# M219X.net
KiCad netlist of a schematic drawn in EAGLE
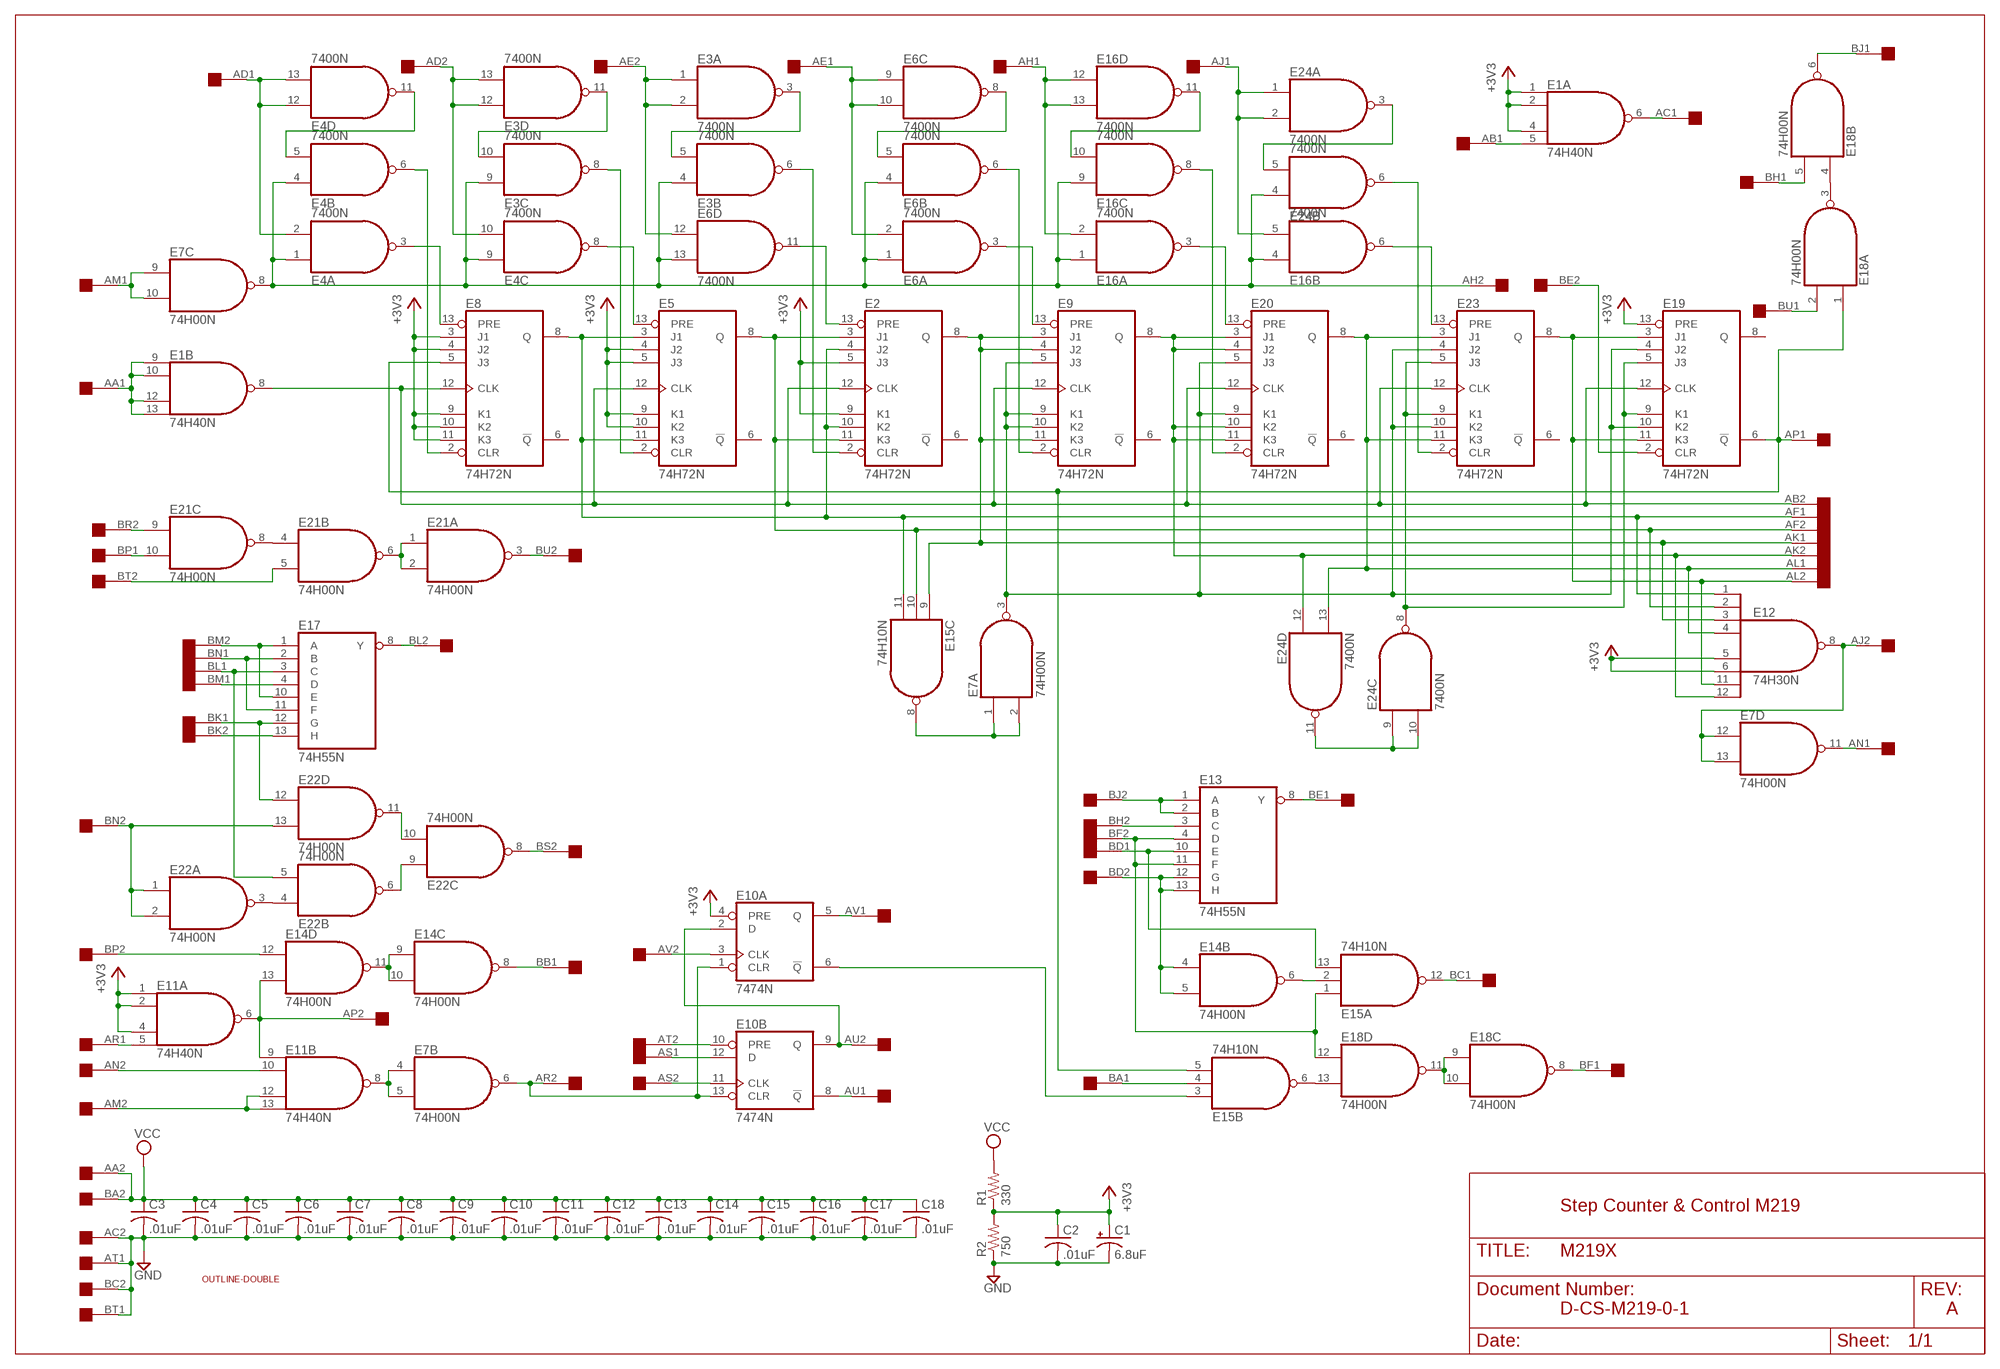
[diagram p0: schematic, sheet 1]

(export (version "E")
  (design (tool "Eeschema 10.0.6"))
  (components
    (comp (ref "C1")
      (value "6.8uF")
      (footprint "eagle-import:E12-8")
      (libsource (lib "eagle-import") (part "CPOL-USE20-8AXIAL"))
    )
    (comp (ref "C2")
      (value ".01uF")
      (footprint "eagle-import:C050-025X075")
      (libsource (lib "eagle-import") (part "C-US050-025X075"))
    )
    (comp (ref "C3")
      (value ".01uF")
      (footprint "eagle-import:C050-025X075")
      (libsource (lib "eagle-import") (part "C-US050-025X075"))
    )
    (comp (ref "C4")
      (value ".01uF")
      (footprint "eagle-import:C050-025X075")
      (libsource (lib "eagle-import") (part "C-US050-025X075"))
    )
    (comp (ref "C5")
      (value ".01uF")
      (footprint "eagle-import:C050-025X075")
      (libsource (lib "eagle-import") (part "C-US050-025X075"))
    )
    (comp (ref "C6")
      (value ".01uF")
      (footprint "eagle-import:C050-025X075")
      (libsource (lib "eagle-import") (part "C-US050-025X075"))
    )
    (comp (ref "C7")
      (value ".01uF")
      (footprint "eagle-import:C050-025X075")
      (libsource (lib "eagle-import") (part "C-US050-025X075"))
    )
    (comp (ref "C8")
      (value ".01uF")
      (footprint "eagle-import:C050-025X075")
      (libsource (lib "eagle-import") (part "C-US050-025X075"))
    )
    (comp (ref "C9")
      (value ".01uF")
      (footprint "eagle-import:C050-025X075")
      (libsource (lib "eagle-import") (part "C-US050-025X075"))
    )
    (comp (ref "C10")
      (value ".01uF")
      (footprint "eagle-import:C050-025X075")
      (libsource (lib "eagle-import") (part "C-US050-025X075"))
    )
    (comp (ref "C11")
      (value ".01uF")
      (footprint "eagle-import:C050-025X075")
      (libsource (lib "eagle-import") (part "C-US050-025X075"))
    )
    (comp (ref "C12")
      (value ".01uF")
      (footprint "eagle-import:C050-025X075")
      (libsource (lib "eagle-import") (part "C-US050-025X075"))
    )
    (comp (ref "C13")
      (value ".01uF")
      (footprint "eagle-import:C050-025X075")
      (libsource (lib "eagle-import") (part "C-US050-025X075"))
    )
    (comp (ref "C14")
      (value ".01uF")
      (footprint "eagle-import:C050-025X075")
      (libsource (lib "eagle-import") (part "C-US050-025X075"))
    )
    (comp (ref "C15")
      (value ".01uF")
      (footprint "eagle-import:C050-025X075")
      (libsource (lib "eagle-import") (part "C-US050-025X075"))
    )
    (comp (ref "C16")
      (value ".01uF")
      (footprint "eagle-import:C050-025X075")
      (libsource (lib "eagle-import") (part "C-US050-025X075"))
    )
    (comp (ref "C17")
      (value ".01uF")
      (footprint "eagle-import:C050-025X075")
      (libsource (lib "eagle-import") (part "C-US050-025X075"))
    )
    (comp (ref "C18")
      (value ".01uF")
      (footprint "eagle-import:C050-025X075")
      (libsource (lib "eagle-import") (part "C-US050-025X075"))
    )
    (comp (ref "E1")
      (value "74H40N")
      (footprint "eagle-import:DIL14")
      (libsource (lib "eagle-import") (part "7440NS"))
    )
    (comp (ref "E2")
      (value "74H72N")
      (footprint "eagle-import:DIL14")
      (libsource (lib "eagle-import") (part "7472N"))
    )
    (comp (ref "E3")
      (value "7400N")
      (footprint "eagle-import:DIL14")
      (libsource (lib "eagle-import") (part "7400NS"))
    )
    (comp (ref "E4")
      (value "7400N")
      (footprint "eagle-import:DIL14")
      (libsource (lib "eagle-import") (part "7400NS"))
    )
    (comp (ref "E5")
      (value "74H72N")
      (footprint "eagle-import:DIL14")
      (libsource (lib "eagle-import") (part "7472N"))
    )
    (comp (ref "E6")
      (value "7400N")
      (footprint "eagle-import:DIL14")
      (libsource (lib "eagle-import") (part "7400NS"))
    )
    (comp (ref "E7")
      (value "74H00N")
      (footprint "eagle-import:DIL14")
      (libsource (lib "eagle-import") (part "7400NS"))
    )
    (comp (ref "E8")
      (value "74H72N")
      (footprint "eagle-import:DIL14")
      (libsource (lib "eagle-import") (part "7472N"))
    )
    (comp (ref "E9")
      (value "74H72N")
      (footprint "eagle-import:DIL14")
      (libsource (lib "eagle-import") (part "7472N"))
    )
    (comp (ref "E10")
      (value "7474N")
      (footprint "eagle-import:DIL14")
      (libsource (lib "eagle-import") (part "7474NS"))
    )
    (comp (ref "E11")
      (value "74H40N")
      (footprint "eagle-import:DIL14")
      (libsource (lib "eagle-import") (part "7440NS"))
    )
    (comp (ref "E12")
      (value "74H30N")
      (footprint "eagle-import:DIL14")
      (libsource (lib "eagle-import") (part "7430NS"))
    )
    (comp (ref "E13")
      (value "74H55N")
      (footprint "eagle-import:DIL14")
      (libsource (lib "eagle-import") (part "7455NLS"))
    )
    (comp (ref "E14")
      (value "74H00N")
      (footprint "eagle-import:DIL14")
      (libsource (lib "eagle-import") (part "7400NS"))
    )
    (comp (ref "E15")
      (value "74H10N")
      (footprint "eagle-import:DIL14")
      (libsource (lib "eagle-import") (part "7410NS"))
    )
    (comp (ref "E16")
      (value "7400N")
      (footprint "eagle-import:DIL14")
      (libsource (lib "eagle-import") (part "7400NS"))
    )
    (comp (ref "E17")
      (value "74H55N")
      (footprint "eagle-import:DIL14")
      (libsource (lib "eagle-import") (part "7455NLS"))
    )
    (comp (ref "E18")
      (value "74H00N")
      (footprint "eagle-import:DIL14")
      (libsource (lib "eagle-import") (part "7400NS"))
    )
    (comp (ref "E19")
      (value "74H72N")
      (footprint "eagle-import:DIL14")
      (libsource (lib "eagle-import") (part "7472N"))
    )
    (comp (ref "E20")
      (value "74H72N")
      (footprint "eagle-import:DIL14")
      (libsource (lib "eagle-import") (part "7472N"))
    )
    (comp (ref "E21")
      (value "74H00N")
      (footprint "eagle-import:DIL14")
      (libsource (lib "eagle-import") (part "7400NS"))
    )
    (comp (ref "E22")
      (value "74H00N")
      (footprint "eagle-import:DIL14")
      (libsource (lib "eagle-import") (part "7400NS"))
    )
    (comp (ref "E23")
      (value "74H72N")
      (footprint "eagle-import:DIL14")
      (libsource (lib "eagle-import") (part "7472N"))
    )
    (comp (ref "E24")
      (value "7400N")
      (footprint "eagle-import:DIL14")
      (libsource (lib "eagle-import") (part "7400NS"))
    )
    (comp (ref "R1")
      (value "330")
      (footprint "eagle-import:0207_10")
      (libsource (lib "eagle-import") (part "R-US_0207/10"))
    )
    (comp (ref "R2")
      (value "750")
      (footprint "eagle-import:0207_10")
      (libsource (lib "eagle-import") (part "R-US_0207/10"))
    )
    (comp (ref "U$1")
      (value "OUTLINE-DOUBLE")
      (footprint "eagle-import:DOUBLE")
      (libsource (lib "eagle-import") (part "OUTLINE-DOUBLE"))
    )
    (comp (ref "U$3")
      (value "DOUBLE")
      (footprint "eagle-import:EDGE-CON4")
      (libsource (lib "eagle-import") (part "DOUBLE"))
    )
  )
  (nets
    (net (code "1") (name "+3V3") (class "Default")
      (node (ref "C1") (pin "+") (pinfunction "+_+") (pintype "passive"))
      (node (ref "C2") (pin "1") (pinfunction "1_1") (pintype "passive"))
      (node (ref "E1") (pin "1") (pinfunction "I0_1") (pintype "input"))
      (node (ref "E1") (pin "2") (pinfunction "I1_2") (pintype "input"))
      (node (ref "E1") (pin "4") (pinfunction "I2_4") (pintype "input"))
      (node (ref "E10") (pin "4") (pinfunction "PRE_4") (pintype "input"))
      (node (ref "E11") (pin "1") (pinfunction "I0_1") (pintype "input"))
      (node (ref "E11") (pin "2") (pinfunction "I1_2") (pintype "input"))
      (node (ref "E11") (pin "4") (pinfunction "I2_4") (pintype "input"))
      (node (ref "E12") (pin "5") (pinfunction "I4_5") (pintype "input"))
      (node (ref "E12") (pin "6") (pinfunction "I5_6") (pintype "input"))
      (node (ref "E19") (pin "13") (pinfunction "PRE_13") (pintype "input"))
      (node (ref "E2") (pin "5") (pinfunction "J3_5") (pintype "input"))
      (node (ref "E2") (pin "9") (pinfunction "K1_9") (pintype "input"))
      (node (ref "E5") (pin "10") (pinfunction "K2_10") (pintype "input"))
      (node (ref "E5") (pin "4") (pinfunction "J2_4") (pintype "input"))
      (node (ref "E5") (pin "5") (pinfunction "J3_5") (pintype "input"))
      (node (ref "E5") (pin "9") (pinfunction "K1_9") (pintype "input"))
      (node (ref "E8") (pin "10") (pinfunction "K2_10") (pintype "input"))
      (node (ref "E8") (pin "11") (pinfunction "K3_11") (pintype "input"))
      (node (ref "E8") (pin "3") (pinfunction "J1_3") (pintype "input"))
      (node (ref "E8") (pin "4") (pinfunction "J2_4") (pintype "input"))
      (node (ref "E8") (pin "9") (pinfunction "K1_9") (pintype "input"))
      (node (ref "R1") (pin "1") (pinfunction "1_1") (pintype "passive"))
      (node (ref "R2") (pin "2") (pinfunction "2_2") (pintype "passive"))
    )
    (net (code "2") (name "GND") (class "Default")
      (node (ref "C1") (pin "-") (pinfunction "-_-") (pintype "passive"))
      (node (ref "C10") (pin "2") (pinfunction "2_2") (pintype "passive"))
      (node (ref "C11") (pin "2") (pinfunction "2_2") (pintype "passive"))
      (node (ref "C12") (pin "2") (pinfunction "2_2") (pintype "passive"))
      (node (ref "C13") (pin "2") (pinfunction "2_2") (pintype "passive"))
      (node (ref "C14") (pin "2") (pinfunction "2_2") (pintype "passive"))
      (node (ref "C15") (pin "2") (pinfunction "2_2") (pintype "passive"))
      (node (ref "C16") (pin "2") (pinfunction "2_2") (pintype "passive"))
      (node (ref "C17") (pin "2") (pinfunction "2_2") (pintype "passive"))
      (node (ref "C18") (pin "2") (pinfunction "2_2") (pintype "passive"))
      (node (ref "C2") (pin "2") (pinfunction "2_2") (pintype "passive"))
      (node (ref "C3") (pin "2") (pinfunction "2_2") (pintype "passive"))
      (node (ref "C4") (pin "2") (pinfunction "2_2") (pintype "passive"))
      (node (ref "C5") (pin "2") (pinfunction "2_2") (pintype "passive"))
      (node (ref "C6") (pin "2") (pinfunction "2_2") (pintype "passive"))
      (node (ref "C7") (pin "2") (pinfunction "2_2") (pintype "passive"))
      (node (ref "C8") (pin "2") (pinfunction "2_2") (pintype "passive"))
      (node (ref "C9") (pin "2") (pinfunction "2_2") (pintype "passive"))
      (node (ref "R2") (pin "1") (pinfunction "1_1") (pintype "passive"))
      (node (ref "U$3") (pin "AC2") (pinfunction "1_AC2") (pintype "bidirectional"))
      (node (ref "U$3") (pin "AT1") (pinfunction "1_AT1") (pintype "bidirectional"))
      (node (ref "U$3") (pin "BC2") (pinfunction "1_BC2") (pintype "bidirectional"))
      (node (ref "U$3") (pin "BT1") (pinfunction "1_BT1") (pintype "bidirectional"))
    )
    (net (code "3") (name "Net-(E1C-I3)") (class "Default")
      (node (ref "E1") (pin "5") (pinfunction "I3_5") (pintype "input"))
      (node (ref "U$3") (pin "AB1") (pinfunction "1_AB1") (pintype "bidirectional"))
    )
    (net (code "4") (name "Net-(E1C-O)") (class "Default")
      (node (ref "E1") (pin "6") (pinfunction "O_6") (pintype "output"))
      (node (ref "U$3") (pin "AC1") (pinfunction "1_AC1") (pintype "bidirectional"))
    )
    (net (code "5") (name "Net-(E1D-I0)") (class "Default")
      (node (ref "E1") (pin "10") (pinfunction "I1_10") (pintype "input"))
      (node (ref "E1") (pin "12") (pinfunction "I2_12") (pintype "input"))
      (node (ref "E1") (pin "13") (pinfunction "I3_13") (pintype "input"))
      (node (ref "E1") (pin "9") (pinfunction "I0_9") (pintype "input"))
      (node (ref "U$3") (pin "AA1") (pinfunction "1_AA1") (pintype "bidirectional"))
    )
    (net (code "6") (name "Net-(E2A-CLR)") (class "Default")
      (node (ref "E2") (pin "2") (pinfunction "CLR_2") (pintype "input"))
      (node (ref "E3") (pin "6") (pinfunction "O_6") (pintype "output"))
    )
    (net (code "7") (name "Net-(E2A-PRE)") (class "Default")
      (node (ref "E2") (pin "13") (pinfunction "PRE_13") (pintype "input"))
      (node (ref "E6") (pin "11") (pinfunction "O_11") (pintype "output"))
    )
    (net (code "8") (name "Net-(E3A-I0)") (class "Default")
      (node (ref "E3") (pin "1") (pinfunction "I0_1") (pintype "input"))
      (node (ref "E3") (pin "2") (pinfunction "I1_2") (pintype "input"))
      (node (ref "E6") (pin "12") (pinfunction "I0_12") (pintype "input"))
      (node (ref "U$3") (pin "AE2") (pinfunction "1_AE2") (pintype "bidirectional"))
    )
    (net (code "9") (name "Net-(E3A-O)") (class "Default")
      (node (ref "E3") (pin "3") (pinfunction "O_3") (pintype "output"))
      (node (ref "E3") (pin "5") (pinfunction "I1_5") (pintype "input"))
    )
    (net (code "10") (name "Net-(E3C-I1)") (class "Default")
      (node (ref "E3") (pin "10") (pinfunction "I1_10") (pintype "input"))
      (node (ref "E3") (pin "11") (pinfunction "O_11") (pintype "output"))
    )
    (net (code "11") (name "Net-(E3C-O)") (class "Default")
      (node (ref "E3") (pin "8") (pinfunction "O_8") (pintype "output"))
      (node (ref "E5") (pin "2") (pinfunction "CLR_2") (pintype "input"))
    )
    (net (code "12") (name "Net-(E3D-I0)") (class "Default")
      (node (ref "E3") (pin "12") (pinfunction "I0_12") (pintype "input"))
      (node (ref "E3") (pin "13") (pinfunction "I1_13") (pintype "input"))
      (node (ref "E4") (pin "10") (pinfunction "I1_10") (pintype "input"))
      (node (ref "U$3") (pin "AD2") (pinfunction "1_AD2") (pintype "bidirectional"))
    )
    (net (code "13") (name "Net-(E4A-I1)") (class "Default")
      (node (ref "E4") (pin "12") (pinfunction "I0_12") (pintype "input"))
      (node (ref "E4") (pin "13") (pinfunction "I1_13") (pintype "input"))
      (node (ref "E4") (pin "2") (pinfunction "I1_2") (pintype "input"))
      (node (ref "U$3") (pin "AD1") (pinfunction "1_AD1") (pintype "bidirectional"))
    )
    (net (code "14") (name "Net-(E4A-O)") (class "Default")
      (node (ref "E4") (pin "3") (pinfunction "O_3") (pintype "output"))
      (node (ref "E8") (pin "13") (pinfunction "PRE_13") (pintype "input"))
    )
    (net (code "15") (name "Net-(E4B-I1)") (class "Default")
      (node (ref "E4") (pin "11") (pinfunction "O_11") (pintype "output"))
      (node (ref "E4") (pin "5") (pinfunction "I1_5") (pintype "input"))
    )
    (net (code "16") (name "Net-(E4B-O)") (class "Default")
      (node (ref "E4") (pin "6") (pinfunction "O_6") (pintype "output"))
      (node (ref "E8") (pin "2") (pinfunction "CLR_2") (pintype "input"))
    )
    (net (code "17") (name "Net-(E4C-O)") (class "Default")
      (node (ref "E4") (pin "8") (pinfunction "O_8") (pintype "output"))
      (node (ref "E5") (pin "13") (pinfunction "PRE_13") (pintype "input"))
    )
    (net (code "18") (name "Net-(E6A-I1)") (class "Default")
      (node (ref "E6") (pin "10") (pinfunction "I1_10") (pintype "input"))
      (node (ref "E6") (pin "2") (pinfunction "I1_2") (pintype "input"))
      (node (ref "E6") (pin "9") (pinfunction "I0_9") (pintype "input"))
      (node (ref "U$3") (pin "AE1") (pinfunction "1_AE1") (pintype "bidirectional"))
    )
    (net (code "19") (name "Net-(E6A-O)") (class "Default")
      (node (ref "E6") (pin "3") (pinfunction "O_3") (pintype "output"))
      (node (ref "E9") (pin "13") (pinfunction "PRE_13") (pintype "input"))
    )
    (net (code "20") (name "Net-(E6B-I1)") (class "Default")
      (node (ref "E6") (pin "5") (pinfunction "I1_5") (pintype "input"))
      (node (ref "E6") (pin "8") (pinfunction "O_8") (pintype "output"))
    )
    (net (code "21") (name "Net-(E6B-O)") (class "Default")
      (node (ref "E6") (pin "6") (pinfunction "O_6") (pintype "output"))
      (node (ref "E9") (pin "2") (pinfunction "CLR_2") (pintype "input"))
    )
    (net (code "22") (name "Net-(E7C-I0)") (class "Default")
      (node (ref "E7") (pin "10") (pinfunction "I1_10") (pintype "input"))
      (node (ref "E7") (pin "9") (pinfunction "I0_9") (pintype "input"))
      (node (ref "U$3") (pin "AM1") (pinfunction "1_AM1") (pintype "bidirectional"))
    )
    (net (code "23") (name "Net-(E7D-O)") (class "Default")
      (node (ref "E7") (pin "11") (pinfunction "O_11") (pintype "output"))
      (node (ref "U$3") (pin "AN1") (pinfunction "1_AN1") (pintype "bidirectional"))
    )
    (net (code "24") (name "Net-(E10A-CLK)") (class "Default")
      (node (ref "E10") (pin "3") (pinfunction "CLK_3") (pintype "input"))
      (node (ref "U$3") (pin "AV2") (pinfunction "1_AV2") (pintype "bidirectional"))
    )
    (net (code "25") (name "Net-(E10A-CLR)") (class "Default")
      (node (ref "E10") (pin "1") (pinfunction "CLR_1") (pintype "input"))
      (node (ref "E10") (pin "13") (pinfunction "CLR_13") (pintype "input"))
      (node (ref "E7") (pin "6") (pinfunction "O_6") (pintype "output"))
      (node (ref "U$3") (pin "AR2") (pinfunction "1_AR2") (pintype "bidirectional"))
    )
    (net (code "26") (name "Net-(E10A-D)") (class "Default")
      (node (ref "E10") (pin "2") (pinfunction "D_2") (pintype "input"))
      (node (ref "E10") (pin "9") (pinfunction "Q_9") (pintype "output"))
      (node (ref "U$3") (pin "AU2") (pinfunction "1_AU2") (pintype "bidirectional"))
    )
    (net (code "27") (name "Net-(E10A-Q)") (class "Default")
      (node (ref "E10") (pin "5") (pinfunction "Q_5") (pintype "output"))
      (node (ref "U$3") (pin "AV1") (pinfunction "1_AV1") (pintype "bidirectional"))
    )
    (net (code "28") (name "Net-(E10A-~{Q})") (class "Default")
      (node (ref "E10") (pin "6") (pinfunction "~{Q}_6") (pintype "output"))
      (node (ref "E15") (pin "3") (pinfunction "I0_3") (pintype "input"))
    )
    (net (code "29") (name "Net-(E10B-CLK)") (class "Default")
      (node (ref "E10") (pin "11") (pinfunction "CLK_11") (pintype "input"))
      (node (ref "U$3") (pin "AS2") (pinfunction "1_AS2") (pintype "bidirectional"))
    )
    (net (code "30") (name "Net-(E10B-D)") (class "Default")
      (node (ref "E10") (pin "12") (pinfunction "D_12") (pintype "input"))
      (node (ref "U$3") (pin "AS1") (pinfunction "1_AS1") (pintype "bidirectional"))
    )
    (net (code "31") (name "Net-(E10B-PRE)") (class "Default")
      (node (ref "E10") (pin "10") (pinfunction "PRE_10") (pintype "input"))
      (node (ref "U$3") (pin "AT2") (pinfunction "1_AT2") (pintype "bidirectional"))
    )
    (net (code "32") (name "Net-(E10B-~{Q})") (class "Default")
      (node (ref "E10") (pin "8") (pinfunction "~{Q}_8") (pintype "output"))
      (node (ref "U$3") (pin "AU1") (pinfunction "1_AU1") (pintype "bidirectional"))
    )
    (net (code "33") (name "Net-(E11C-I3)") (class "Default")
      (node (ref "E11") (pin "5") (pinfunction "I3_5") (pintype "input"))
      (node (ref "U$3") (pin "AR1") (pinfunction "1_AR1") (pintype "bidirectional"))
    )
    (net (code "34") (name "Net-(E11C-O)") (class "Default")
      (node (ref "E11") (pin "6") (pinfunction "O_6") (pintype "output"))
      (node (ref "E11") (pin "9") (pinfunction "I0_9") (pintype "input"))
      (node (ref "E14") (pin "13") (pinfunction "I1_13") (pintype "input"))
      (node (ref "U$3") (pin "AP2") (pinfunction "1_AP2") (pintype "bidirectional"))
    )
    (net (code "35") (name "Net-(E11D-I1)") (class "Default")
      (node (ref "E11") (pin "10") (pinfunction "I1_10") (pintype "input"))
      (node (ref "U$3") (pin "AN2") (pinfunction "1_AN2") (pintype "bidirectional"))
    )
    (net (code "36") (name "Net-(E11D-I2)") (class "Default")
      (node (ref "E11") (pin "12") (pinfunction "I2_12") (pintype "input"))
      (node (ref "E11") (pin "13") (pinfunction "I3_13") (pintype "input"))
      (node (ref "U$3") (pin "AM2") (pinfunction "1_AM2") (pintype "bidirectional"))
    )
    (net (code "37") (name "Net-(E11D-O)") (class "Default")
      (node (ref "E11") (pin "8") (pinfunction "O_8") (pintype "output"))
      (node (ref "E7") (pin "4") (pinfunction "I0_4") (pintype "input"))
      (node (ref "E7") (pin "5") (pinfunction "I1_5") (pintype "input"))
    )
    (net (code "38") (name "Net-(E12D-I0)") (class "Default")
      (node (ref "E12") (pin "1") (pinfunction "I0_1") (pintype "input"))
      (node (ref "E15") (pin "11") (pinfunction "I2_11") (pintype "input"))
      (node (ref "E2") (pin "10") (pinfunction "K2_10") (pintype "input"))
      (node (ref "E2") (pin "4") (pinfunction "J2_4") (pintype "input"))
      (node (ref "E5") (pin "11") (pinfunction "K3_11") (pintype "input"))
      (node (ref "E5") (pin "3") (pinfunction "J1_3") (pintype "input"))
      (node (ref "E8") (pin "8") (pinfunction "Q_8") (pintype "output"))
      (node (ref "U$3") (pin "AF1") (pinfunction "1_AF1") (pintype "bidirectional"))
    )
    (net (code "39") (name "Net-(E12D-I1)") (class "Default")
      (node (ref "E12") (pin "2") (pinfunction "I1_2") (pintype "input"))
      (node (ref "E15") (pin "10") (pinfunction "I1_10") (pintype "input"))
      (node (ref "E2") (pin "11") (pinfunction "K3_11") (pintype "input"))
      (node (ref "E2") (pin "3") (pinfunction "J1_3") (pintype "input"))
      (node (ref "E5") (pin "8") (pinfunction "Q_8") (pintype "output"))
      (node (ref "U$3") (pin "AF2") (pinfunction "1_AF2") (pintype "bidirectional"))
    )
    (net (code "40") (name "Net-(E12D-I2)") (class "Default")
      (node (ref "E12") (pin "3") (pinfunction "I2_3") (pintype "input"))
      (node (ref "E15") (pin "9") (pinfunction "I0_9") (pintype "input"))
      (node (ref "E2") (pin "8") (pinfunction "Q_8") (pintype "output"))
      (node (ref "E9") (pin "11") (pinfunction "K3_11") (pintype "input"))
      (node (ref "E9") (pin "3") (pinfunction "J1_3") (pintype "input"))
      (node (ref "E9") (pin "4") (pinfunction "J2_4") (pintype "input"))
      (node (ref "U$3") (pin "AK1") (pinfunction "1_AK1") (pintype "bidirectional"))
    )
    (net (code "41") (name "Net-(E12D-I3)") (class "Default")
      (node (ref "E12") (pin "4") (pinfunction "I3_4") (pintype "input"))
      (node (ref "E20") (pin "8") (pinfunction "Q_8") (pintype "output"))
      (node (ref "E23") (pin "11") (pinfunction "K3_11") (pintype "input"))
      (node (ref "E23") (pin "3") (pinfunction "J1_3") (pintype "input"))
      (node (ref "E24") (pin "13") (pinfunction "I1_13") (pintype "input"))
      (node (ref "U$3") (pin "AL1") (pinfunction "1_AL1") (pintype "bidirectional"))
    )
    (net (code "42") (name "Net-(E12D-I6)") (class "Default")
      (node (ref "E12") (pin "11") (pinfunction "I6_11") (pintype "input"))
      (node (ref "E19") (pin "11") (pinfunction "K3_11") (pintype "input"))
      (node (ref "E19") (pin "3") (pinfunction "J1_3") (pintype "input"))
      (node (ref "E23") (pin "8") (pinfunction "Q_8") (pintype "output"))
      (node (ref "U$3") (pin "AL2") (pinfunction "1_AL2") (pintype "bidirectional"))
    )
    (net (code "43") (name "Net-(E12D-I7)") (class "Default")
      (node (ref "E12") (pin "12") (pinfunction "I7_12") (pintype "input"))
      (node (ref "E20") (pin "10") (pinfunction "K2_10") (pintype "input"))
      (node (ref "E20") (pin "11") (pinfunction "K3_11") (pintype "input"))
      (node (ref "E20") (pin "3") (pinfunction "J1_3") (pintype "input"))
      (node (ref "E20") (pin "4") (pinfunction "J2_4") (pintype "input"))
      (node (ref "E24") (pin "12") (pinfunction "I0_12") (pintype "input"))
      (node (ref "E9") (pin "8") (pinfunction "Q_8") (pintype "output"))
      (node (ref "U$3") (pin "AK2") (pinfunction "1_AK2") (pintype "bidirectional"))
    )
    (net (code "44") (name "Net-(E12D-O)") (class "Default")
      (node (ref "E12") (pin "8") (pinfunction "O_8") (pintype "output"))
      (node (ref "E7") (pin "12") (pinfunction "I0_12") (pintype "input"))
      (node (ref "E7") (pin "13") (pinfunction "I1_13") (pintype "input"))
      (node (ref "U$3") (pin "AJ2") (pinfunction "1_AJ2") (pintype "bidirectional"))
    )
    (net (code "45") (name "Net-(E13A-A)") (class "Default")
      (node (ref "E13") (pin "1") (pinfunction "A_1") (pintype "input"))
      (node (ref "E13") (pin "2") (pinfunction "B_2") (pintype "input"))
      (node (ref "U$3") (pin "BJ2") (pinfunction "1_BJ2") (pintype "bidirectional"))
    )
    (net (code "46") (name "Net-(E13A-C)") (class "Default")
      (node (ref "E13") (pin "3") (pinfunction "C_3") (pintype "input"))
      (node (ref "U$3") (pin "BH2") (pinfunction "1_BH2") (pintype "bidirectional"))
    )
    (net (code "47") (name "Net-(E13A-D)") (class "Default")
      (node (ref "E13") (pin "11") (pinfunction "F_11") (pintype "input"))
      (node (ref "E13") (pin "4") (pinfunction "D_4") (pintype "input"))
      (node (ref "E15") (pin "1") (pinfunction "I0_1") (pintype "input"))
      (node (ref "E18") (pin "12") (pinfunction "I0_12") (pintype "input"))
      (node (ref "U$3") (pin "BF2") (pinfunction "1_BF2") (pintype "bidirectional"))
    )
    (net (code "48") (name "Net-(E13A-E)") (class "Default")
      (node (ref "E13") (pin "10") (pinfunction "E_10") (pintype "input"))
      (node (ref "E15") (pin "13") (pinfunction "I2_13") (pintype "input"))
      (node (ref "U$3") (pin "BD1") (pinfunction "1_BD1") (pintype "bidirectional"))
    )
    (net (code "49") (name "Net-(E13A-G)") (class "Default")
      (node (ref "E13") (pin "12") (pinfunction "G_12") (pintype "input"))
      (node (ref "E13") (pin "13") (pinfunction "H_13") (pintype "input"))
      (node (ref "E14") (pin "4") (pinfunction "I0_4") (pintype "input"))
      (node (ref "E14") (pin "5") (pinfunction "I1_5") (pintype "input"))
      (node (ref "U$3") (pin "BD2") (pinfunction "1_BD2") (pintype "bidirectional"))
    )
    (net (code "50") (name "Net-(E13A-Y)") (class "Default")
      (node (ref "E13") (pin "8") (pinfunction "Y_8") (pintype "output"))
      (node (ref "U$3") (pin "BE1") (pinfunction "1_BE1") (pintype "bidirectional"))
    )
    (net (code "51") (name "Net-(E14B-O)") (class "Default")
      (node (ref "E14") (pin "6") (pinfunction "O_6") (pintype "output"))
      (node (ref "E15") (pin "2") (pinfunction "I1_2") (pintype "input"))
    )
    (net (code "52") (name "Net-(E14C-I0)") (class "Default")
      (node (ref "E14") (pin "10") (pinfunction "I1_10") (pintype "input"))
      (node (ref "E14") (pin "11") (pinfunction "O_11") (pintype "output"))
      (node (ref "E14") (pin "9") (pinfunction "I0_9") (pintype "input"))
    )
    (net (code "53") (name "Net-(E14C-O)") (class "Default")
      (node (ref "E14") (pin "8") (pinfunction "O_8") (pintype "output"))
      (node (ref "U$3") (pin "BB1") (pinfunction "1_BB1") (pintype "bidirectional"))
    )
    (net (code "54") (name "Net-(E14D-I0)") (class "Default")
      (node (ref "E14") (pin "12") (pinfunction "I0_12") (pintype "input"))
      (node (ref "U$3") (pin "BP2") (pinfunction "1_BP2") (pintype "bidirectional"))
    )
    (net (code "55") (name "Net-(E15A-O)") (class "Default")
      (node (ref "E15") (pin "12") (pinfunction "O_12") (pintype "output"))
      (node (ref "U$3") (pin "BC1") (pinfunction "1_BC1") (pintype "bidirectional"))
    )
    (net (code "56") (name "Net-(E15B-I1)") (class "Default")
      (node (ref "E15") (pin "4") (pinfunction "I1_4") (pintype "input"))
      (node (ref "U$3") (pin "BA1") (pinfunction "1_BA1") (pintype "bidirectional"))
    )
    (net (code "57") (name "Net-(E15B-I2)") (class "Default")
      (node (ref "E15") (pin "5") (pinfunction "I2_5") (pintype "input"))
      (node (ref "E18") (pin "1") (pinfunction "I0_1") (pintype "input"))
      (node (ref "E19") (pin "6") (pinfunction "~{Q}_6") (pintype "output"))
      (node (ref "E8") (pin "5") (pinfunction "J3_5") (pintype "input"))
      (node (ref "U$3") (pin "AP1") (pinfunction "1_AP1") (pintype "bidirectional"))
    )
    (net (code "58") (name "Net-(E15B-O)") (class "Default")
      (node (ref "E15") (pin "6") (pinfunction "O_6") (pintype "output"))
      (node (ref "E18") (pin "13") (pinfunction "I1_13") (pintype "input"))
    )
    (net (code "59") (name "Net-(E15C-O)") (class "Default")
      (node (ref "E15") (pin "8") (pinfunction "O_8") (pintype "output"))
      (node (ref "E7") (pin "1") (pinfunction "I0_1") (pintype "input"))
      (node (ref "E7") (pin "2") (pinfunction "I1_2") (pintype "input"))
    )
    (net (code "60") (name "Net-(E16A-I0)") (class "Default")
      (node (ref "E16") (pin "1") (pinfunction "I0_1") (pintype "input"))
      (node (ref "E16") (pin "4") (pinfunction "I0_4") (pintype "input"))
      (node (ref "E16") (pin "9") (pinfunction "I0_9") (pintype "input"))
      (node (ref "E24") (pin "4") (pinfunction "I0_4") (pintype "input"))
      (node (ref "E3") (pin "4") (pinfunction "I0_4") (pintype "input"))
      (node (ref "E3") (pin "9") (pinfunction "I0_9") (pintype "input"))
      (node (ref "E4") (pin "1") (pinfunction "I0_1") (pintype "input"))
      (node (ref "E4") (pin "4") (pinfunction "I0_4") (pintype "input"))
      (node (ref "E4") (pin "9") (pinfunction "I0_9") (pintype "input"))
      (node (ref "E6") (pin "1") (pinfunction "I0_1") (pintype "input"))
      (node (ref "E6") (pin "13") (pinfunction "I1_13") (pintype "input"))
      (node (ref "E6") (pin "4") (pinfunction "I0_4") (pintype "input"))
      (node (ref "E7") (pin "8") (pinfunction "O_8") (pintype "output"))
      (node (ref "U$3") (pin "AH2") (pinfunction "1_AH2") (pintype "bidirectional"))
    )
    (net (code "61") (name "Net-(E16A-I1)") (class "Default")
      (node (ref "E16") (pin "12") (pinfunction "I0_12") (pintype "input"))
      (node (ref "E16") (pin "13") (pinfunction "I1_13") (pintype "input"))
      (node (ref "E16") (pin "2") (pinfunction "I1_2") (pintype "input"))
      (node (ref "U$3") (pin "AH1") (pinfunction "1_AH1") (pintype "bidirectional"))
    )
    (net (code "62") (name "Net-(E16A-O)") (class "Default")
      (node (ref "E16") (pin "3") (pinfunction "O_3") (pintype "output"))
      (node (ref "E20") (pin "13") (pinfunction "PRE_13") (pintype "input"))
    )
    (net (code "63") (name "Net-(E16B-I1)") (class "Default")
      (node (ref "E16") (pin "5") (pinfunction "I1_5") (pintype "input"))
      (node (ref "E24") (pin "1") (pinfunction "I0_1") (pintype "input"))
      (node (ref "E24") (pin "2") (pinfunction "I1_2") (pintype "input"))
      (node (ref "U$3") (pin "AJ1") (pinfunction "1_AJ1") (pintype "bidirectional"))
    )
    (net (code "64") (name "Net-(E16B-O)") (class "Default")
      (node (ref "E16") (pin "6") (pinfunction "O_6") (pintype "output"))
      (node (ref "E23") (pin "13") (pinfunction "PRE_13") (pintype "input"))
    )
    (net (code "65") (name "Net-(E16C-I1)") (class "Default")
      (node (ref "E16") (pin "10") (pinfunction "I1_10") (pintype "input"))
      (node (ref "E16") (pin "11") (pinfunction "O_11") (pintype "output"))
    )
    (net (code "66") (name "Net-(E16C-O)") (class "Default")
      (node (ref "E16") (pin "8") (pinfunction "O_8") (pintype "output"))
      (node (ref "E20") (pin "2") (pinfunction "CLR_2") (pintype "input"))
    )
    (net (code "67") (name "Net-(E17A-A)") (class "Default")
      (node (ref "E17") (pin "1") (pinfunction "A_1") (pintype "input"))
      (node (ref "E17") (pin "10") (pinfunction "E_10") (pintype "input"))
      (node (ref "U$3") (pin "BM2") (pinfunction "1_BM2") (pintype "bidirectional"))
    )
    (net (code "68") (name "Net-(E17A-B)") (class "Default")
      (node (ref "E17") (pin "11") (pinfunction "F_11") (pintype "input"))
      (node (ref "E17") (pin "2") (pinfunction "B_2") (pintype "input"))
      (node (ref "U$3") (pin "BN1") (pinfunction "1_BN1") (pintype "bidirectional"))
    )
    (net (code "69") (name "Net-(E17A-C)") (class "Default")
      (node (ref "E17") (pin "3") (pinfunction "C_3") (pintype "input"))
      (node (ref "E22") (pin "5") (pinfunction "I1_5") (pintype "input"))
      (node (ref "U$3") (pin "BL1") (pinfunction "1_BL1") (pintype "bidirectional"))
    )
    (net (code "70") (name "Net-(E17A-D)") (class "Default")
      (node (ref "E17") (pin "4") (pinfunction "D_4") (pintype "input"))
      (node (ref "U$3") (pin "BM1") (pinfunction "1_BM1") (pintype "bidirectional"))
    )
    (net (code "71") (name "Net-(E17A-G)") (class "Default")
      (node (ref "E17") (pin "12") (pinfunction "G_12") (pintype "input"))
      (node (ref "E22") (pin "12") (pinfunction "I0_12") (pintype "input"))
      (node (ref "U$3") (pin "BK1") (pinfunction "1_BK1") (pintype "bidirectional"))
    )
    (net (code "72") (name "Net-(E17A-H)") (class "Default")
      (node (ref "E17") (pin "13") (pinfunction "H_13") (pintype "input"))
      (node (ref "U$3") (pin "BK2") (pinfunction "1_BK2") (pintype "bidirectional"))
    )
    (net (code "73") (name "Net-(E17A-Y)") (class "Default")
      (node (ref "E17") (pin "8") (pinfunction "Y_8") (pintype "output"))
      (node (ref "U$3") (pin "BL2") (pinfunction "1_BL2") (pintype "bidirectional"))
    )
    (net (code "74") (name "Net-(E18A-I1)") (class "Default")
      (node (ref "E18") (pin "2") (pinfunction "I1_2") (pintype "input"))
      (node (ref "U$3") (pin "BU1") (pinfunction "1_BU1") (pintype "bidirectional"))
    )
    (net (code "75") (name "Net-(E18A-O)") (class "Default")
      (node (ref "E18") (pin "3") (pinfunction "O_3") (pintype "output"))
      (node (ref "E18") (pin "4") (pinfunction "I0_4") (pintype "input"))
    )
    (net (code "76") (name "Net-(E18B-I1)") (class "Default")
      (node (ref "E18") (pin "5") (pinfunction "I1_5") (pintype "input"))
      (node (ref "U$3") (pin "BH1") (pinfunction "1_BH1") (pintype "bidirectional"))
    )
    (net (code "77") (name "Net-(E18B-O)") (class "Default")
      (node (ref "E18") (pin "6") (pinfunction "O_6") (pintype "output"))
      (node (ref "U$3") (pin "BJ1") (pinfunction "1_BJ1") (pintype "bidirectional"))
    )
    (net (code "78") (name "Net-(E18C-I0)") (class "Default")
      (node (ref "E18") (pin "10") (pinfunction "I1_10") (pintype "input"))
      (node (ref "E18") (pin "11") (pinfunction "O_11") (pintype "output"))
      (node (ref "E18") (pin "9") (pinfunction "I0_9") (pintype "input"))
    )
    (net (code "79") (name "Net-(E18C-O)") (class "Default")
      (node (ref "E18") (pin "8") (pinfunction "O_8") (pintype "output"))
      (node (ref "U$3") (pin "BF1") (pinfunction "1_BF1") (pintype "bidirectional"))
    )
    (net (code "80") (name "Net-(E19A-CLK)") (class "Default")
      (node (ref "E1") (pin "8") (pinfunction "O_8") (pintype "output"))
      (node (ref "E19") (pin "12") (pinfunction "CLK_12") (pintype "input"))
      (node (ref "E2") (pin "12") (pinfunction "CLK_12") (pintype "input"))
      (node (ref "E20") (pin "12") (pinfunction "CLK_12") (pintype "input"))
      (node (ref "E23") (pin "12") (pinfunction "CLK_12") (pintype "input"))
      (node (ref "E5") (pin "12") (pinfunction "CLK_12") (pintype "input"))
      (node (ref "E8") (pin "12") (pinfunction "CLK_12") (pintype "input"))
      (node (ref "E9") (pin "12") (pinfunction "CLK_12") (pintype "input"))
      (node (ref "U$3") (pin "AB2") (pinfunction "1_AB2") (pintype "bidirectional"))
    )
    (net (code "81") (name "Net-(E19A-CLR)") (class "Default")
      (node (ref "E19") (pin "2") (pinfunction "CLR_2") (pintype "input"))
      (node (ref "U$3") (pin "BE2") (pinfunction "1_BE2") (pintype "bidirectional"))
    )
    (net (code "82") (name "Net-(E19A-J2)") (class "Default")
      (node (ref "E19") (pin "10") (pinfunction "K2_10") (pintype "input"))
      (node (ref "E19") (pin "4") (pinfunction "J2_4") (pintype "input"))
      (node (ref "E20") (pin "5") (pinfunction "J3_5") (pintype "input"))
      (node (ref "E20") (pin "9") (pinfunction "K1_9") (pintype "input"))
      (node (ref "E23") (pin "10") (pinfunction "K2_10") (pintype "input"))
      (node (ref "E23") (pin "4") (pinfunction "J2_4") (pintype "input"))
      (node (ref "E7") (pin "3") (pinfunction "O_3") (pintype "output"))
      (node (ref "E9") (pin "10") (pinfunction "K2_10") (pintype "input"))
      (node (ref "E9") (pin "5") (pinfunction "J3_5") (pintype "input"))
      (node (ref "E9") (pin "9") (pinfunction "K1_9") (pintype "input"))
    )
    (net (code "83") (name "Net-(E19A-J3)") (class "Default")
      (node (ref "E19") (pin "5") (pinfunction "J3_5") (pintype "input"))
      (node (ref "E19") (pin "9") (pinfunction "K1_9") (pintype "input"))
      (node (ref "E23") (pin "5") (pinfunction "J3_5") (pintype "input"))
      (node (ref "E23") (pin "9") (pinfunction "K1_9") (pintype "input"))
      (node (ref "E24") (pin "8") (pinfunction "O_8") (pintype "output"))
    )
    (net (code "84") (name "Net-(E21A-I0)") (class "Default")
      (node (ref "E21") (pin "1") (pinfunction "I0_1") (pintype "input"))
      (node (ref "E21") (pin "2") (pinfunction "I1_2") (pintype "input"))
      (node (ref "E21") (pin "6") (pinfunction "O_6") (pintype "output"))
    )
    (net (code "85") (name "Net-(E21A-O)") (class "Default")
      (node (ref "E21") (pin "3") (pinfunction "O_3") (pintype "output"))
      (node (ref "U$3") (pin "BU2") (pinfunction "1_BU2") (pintype "bidirectional"))
    )
    (net (code "86") (name "Net-(E21B-I0)") (class "Default")
      (node (ref "E21") (pin "4") (pinfunction "I0_4") (pintype "input"))
      (node (ref "E21") (pin "8") (pinfunction "O_8") (pintype "output"))
    )
    (net (code "87") (name "Net-(E21B-I1)") (class "Default")
      (node (ref "E21") (pin "5") (pinfunction "I1_5") (pintype "input"))
      (node (ref "U$3") (pin "BT2") (pinfunction "1_BT2") (pintype "bidirectional"))
    )
    (net (code "88") (name "Net-(E21C-I0)") (class "Default")
      (node (ref "E21") (pin "9") (pinfunction "I0_9") (pintype "input"))
      (node (ref "U$3") (pin "BR2") (pinfunction "1_BR2") (pintype "bidirectional"))
    )
    (net (code "89") (name "Net-(E21C-I1)") (class "Default")
      (node (ref "E21") (pin "10") (pinfunction "I1_10") (pintype "input"))
      (node (ref "U$3") (pin "BP1") (pinfunction "1_BP1") (pintype "bidirectional"))
    )
    (net (code "90") (name "Net-(E22A-I0)") (class "Default")
      (node (ref "E22") (pin "1") (pinfunction "I0_1") (pintype "input"))
      (node (ref "E22") (pin "13") (pinfunction "I1_13") (pintype "input"))
      (node (ref "E22") (pin "2") (pinfunction "I1_2") (pintype "input"))
      (node (ref "U$3") (pin "BN2") (pinfunction "1_BN2") (pintype "bidirectional"))
    )
    (net (code "91") (name "Net-(E22A-O)") (class "Default")
      (node (ref "E22") (pin "3") (pinfunction "O_3") (pintype "output"))
      (node (ref "E22") (pin "4") (pinfunction "I0_4") (pintype "input"))
    )
    (net (code "92") (name "Net-(E22B-O)") (class "Default")
      (node (ref "E22") (pin "6") (pinfunction "O_6") (pintype "output"))
      (node (ref "E22") (pin "9") (pinfunction "I0_9") (pintype "input"))
    )
    (net (code "93") (name "Net-(E22C-I1)") (class "Default")
      (node (ref "E22") (pin "10") (pinfunction "I1_10") (pintype "input"))
      (node (ref "E22") (pin "11") (pinfunction "O_11") (pintype "output"))
    )
    (net (code "94") (name "Net-(E22C-O)") (class "Default")
      (node (ref "E22") (pin "8") (pinfunction "O_8") (pintype "output"))
      (node (ref "U$3") (pin "BS2") (pinfunction "1_BS2") (pintype "bidirectional"))
    )
    (net (code "95") (name "Net-(E23A-CLR)") (class "Default")
      (node (ref "E23") (pin "2") (pinfunction "CLR_2") (pintype "input"))
      (node (ref "E24") (pin "6") (pinfunction "O_6") (pintype "output"))
    )
    (net (code "96") (name "Net-(E24A-O)") (class "Default")
      (node (ref "E24") (pin "3") (pinfunction "O_3") (pintype "output"))
      (node (ref "E24") (pin "5") (pinfunction "I1_5") (pintype "input"))
    )
    (net (code "97") (name "Net-(E24C-I0)") (class "Default")
      (node (ref "E24") (pin "10") (pinfunction "I1_10") (pintype "input"))
      (node (ref "E24") (pin "11") (pinfunction "O_11") (pintype "output"))
      (node (ref "E24") (pin "9") (pinfunction "I0_9") (pintype "input"))
    )
    (net (code "98") (name "VCC") (class "Default")
      (node (ref "C10") (pin "1") (pinfunction "1_1") (pintype "passive"))
      (node (ref "C11") (pin "1") (pinfunction "1_1") (pintype "passive"))
      (node (ref "C12") (pin "1") (pinfunction "1_1") (pintype "passive"))
      (node (ref "C13") (pin "1") (pinfunction "1_1") (pintype "passive"))
      (node (ref "C14") (pin "1") (pinfunction "1_1") (pintype "passive"))
      (node (ref "C15") (pin "1") (pinfunction "1_1") (pintype "passive"))
      (node (ref "C16") (pin "1") (pinfunction "1_1") (pintype "passive"))
      (node (ref "C17") (pin "1") (pinfunction "1_1") (pintype "passive"))
      (node (ref "C18") (pin "1") (pinfunction "1_1") (pintype "passive"))
      (node (ref "C3") (pin "1") (pinfunction "1_1") (pintype "passive"))
      (node (ref "C4") (pin "1") (pinfunction "1_1") (pintype "passive"))
      (node (ref "C5") (pin "1") (pinfunction "1_1") (pintype "passive"))
      (node (ref "C6") (pin "1") (pinfunction "1_1") (pintype "passive"))
      (node (ref "C7") (pin "1") (pinfunction "1_1") (pintype "passive"))
      (node (ref "C8") (pin "1") (pinfunction "1_1") (pintype "passive"))
      (node (ref "C9") (pin "1") (pinfunction "1_1") (pintype "passive"))
      (node (ref "R1") (pin "2") (pinfunction "2_2") (pintype "passive"))
      (node (ref "U$3") (pin "AA2") (pinfunction "1_AA2") (pintype "bidirectional"))
      (node (ref "U$3") (pin "BA2") (pinfunction "1_BA2") (pintype "bidirectional"))
    )
    (net (code "99") (name "unconnected-(E2A-~{Q}-Pad6)") (class "Default")
      (node (ref "E2") (pin "6") (pinfunction "~{Q}_6") (pintype "output"))
    )
    (net (code "100") (name "unconnected-(E5A-~{Q}-Pad6)") (class "Default")
      (node (ref "E5") (pin "6") (pinfunction "~{Q}_6") (pintype "output"))
    )
    (net (code "101") (name "unconnected-(E8A-~{Q}-Pad6)") (class "Default")
      (node (ref "E8") (pin "6") (pinfunction "~{Q}_6") (pintype "output"))
    )
    (net (code "102") (name "unconnected-(E9A-~{Q}-Pad6)") (class "Default")
      (node (ref "E9") (pin "6") (pinfunction "~{Q}_6") (pintype "output"))
    )
    (net (code "103") (name "unconnected-(E19A-Q-Pad8)") (class "Default")
      (node (ref "E19") (pin "8") (pinfunction "Q_8") (pintype "output"))
    )
    (net (code "104") (name "unconnected-(E20A-~{Q}-Pad6)") (class "Default")
      (node (ref "E20") (pin "6") (pinfunction "~{Q}_6") (pintype "output"))
    )
    (net (code "105") (name "unconnected-(E23A-~{Q}-Pad6)") (class "Default")
      (node (ref "E23") (pin "6") (pinfunction "~{Q}_6") (pintype "output"))
    )
  )
)
